# circuit.net
KiCad netlist of a schematic drawn in EAGLE
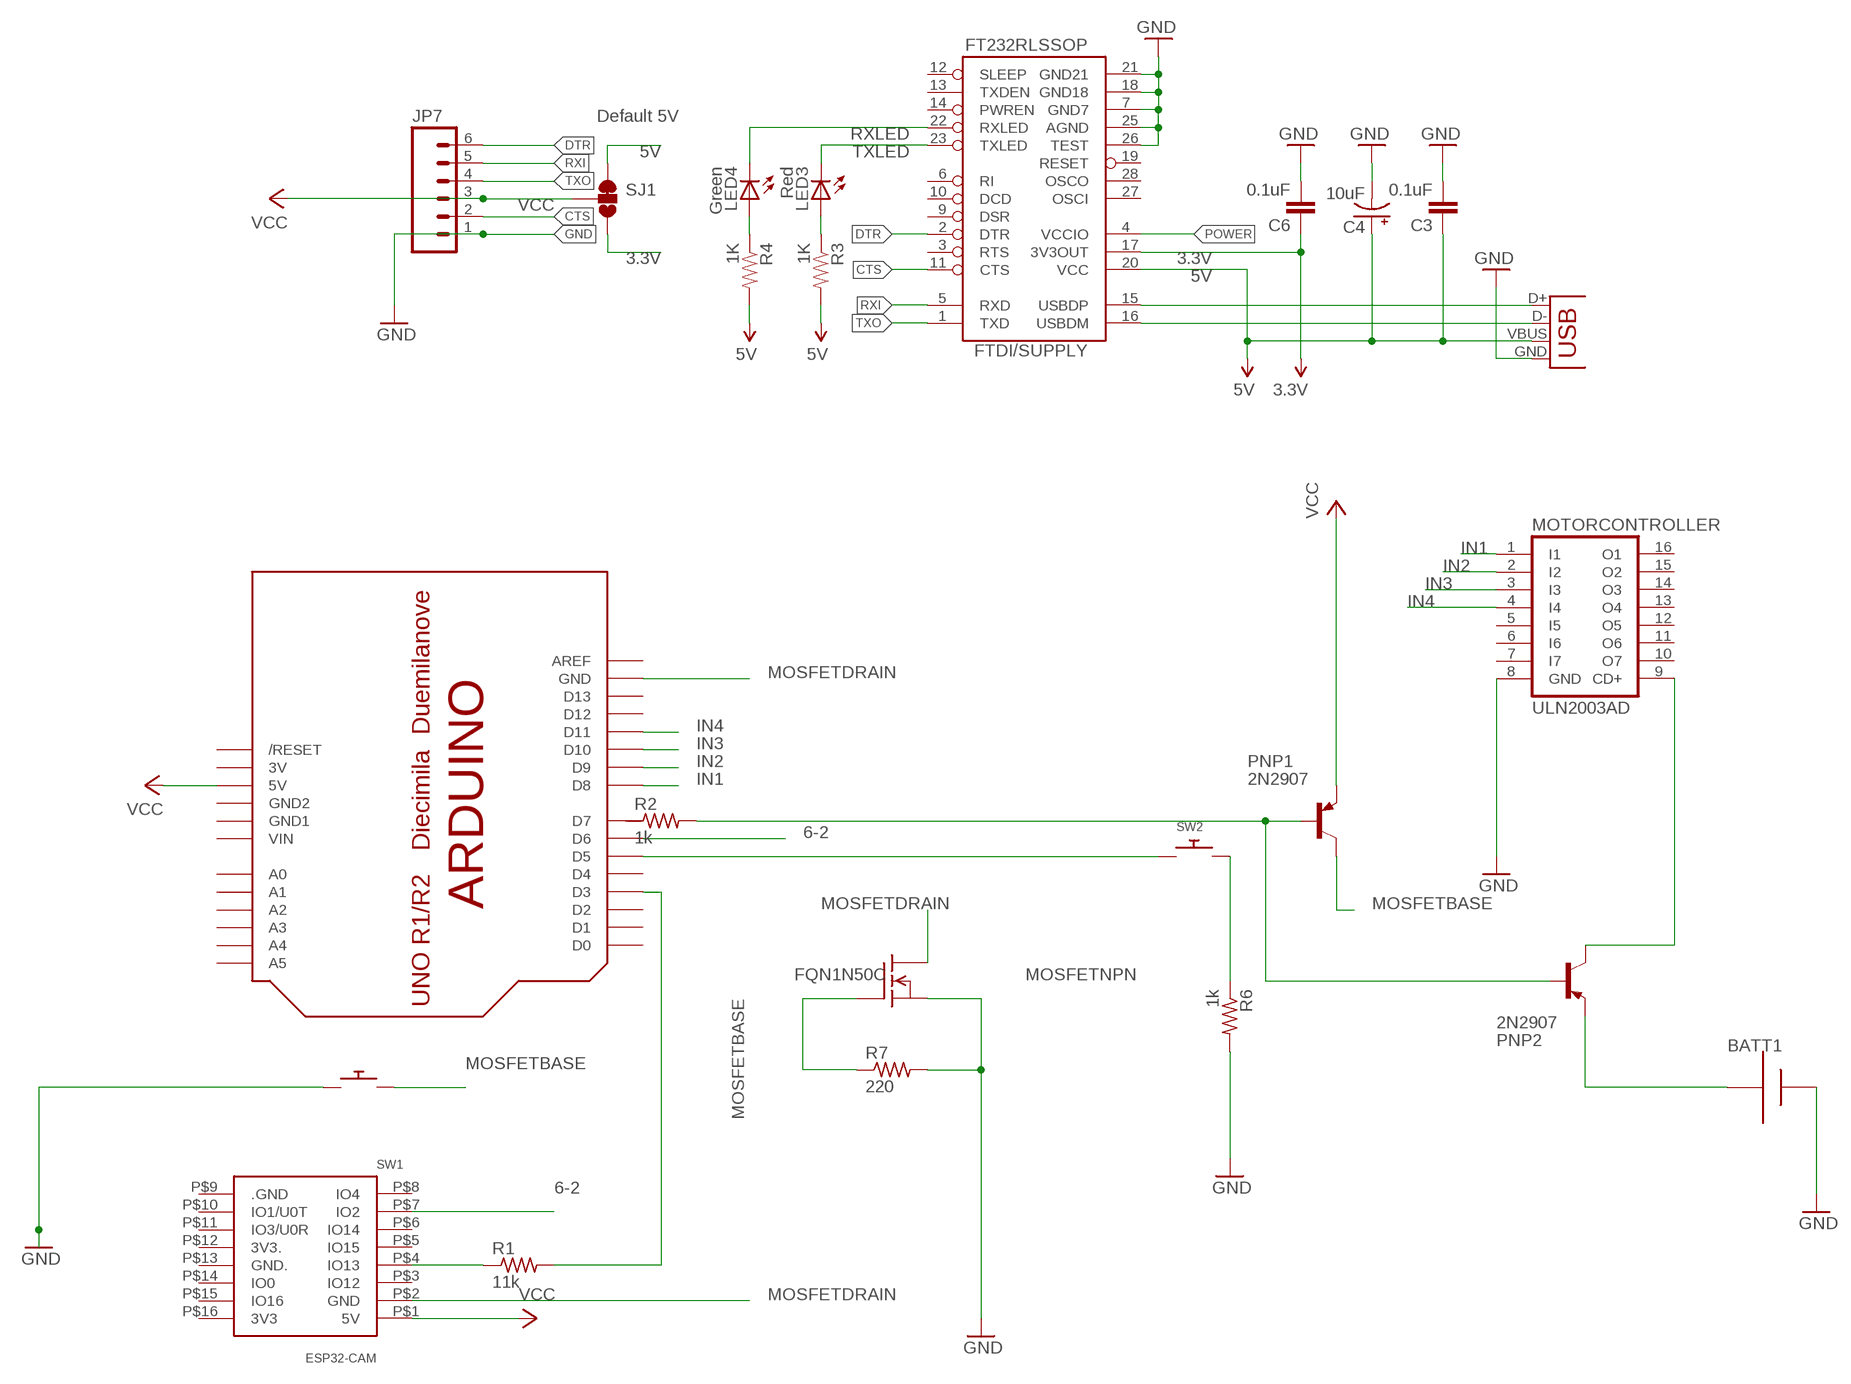
[diagram p0: schematic, sheet 1]

(export (version "E")
  (design (tool "Eeschema 10.0.6"))
  (components
    (comp (ref "BATT1")
      (value "AAA")
      (footprint "eagle-import:12BH412")
      (libsource (lib "eagle-import") (part "AAA"))
    )
    (comp (ref "C3")
      (value "0.1uF")
      (footprint "eagle-import:0603-CAP")
      (libsource (lib "eagle-import") (part "CAP0603-CAP"))
    )
    (comp (ref "C4")
      (value "10uF")
      (footprint "eagle-import:EIA3216")
      (libsource (lib "eagle-import") (part "CAP_POL1206"))
    )
    (comp (ref "C6")
      (value "0.1uF")
      (footprint "eagle-import:0603-CAP")
      (libsource (lib "eagle-import") (part "CAP0603-CAP"))
    )
    (comp (ref "ESP32-CAM")
      (value "ESP32-CAM")
      (footprint "eagle-import:ESP32-CAM")
      (fields (field (name "MF") "AI-Thinker"))
      (libsource (lib "eagle-import") (part "ESP32-CAM"))
    )
    (comp (ref "FTDI/SUPPLY")
      (value "FT232RLSSOP")
      (footprint "eagle-import:SSOP28DB")
      (libsource (lib "eagle-import") (part "FT232RLSSOP"))
    )
    (comp (ref "JP7")
      (value "M06SMD-FEMALE-V2")
      (footprint "eagle-import:1X06-SMD-FEMALE-V2")
      (libsource (lib "eagle-import") (part "M06SMD-FEMALE-V2"))
    )
    (comp (ref "LED3")
      (value "Red")
      (footprint "eagle-import:LED-0603")
      (libsource (lib "eagle-import") (part "LED0603"))
    )
    (comp (ref "LED4")
      (value "Green")
      (footprint "eagle-import:LED-0603")
      (libsource (lib "eagle-import") (part "LED0603"))
    )
    (comp (ref "MOSFETNPN")
      (value "FQN1N50C")
      (footprint "eagle-import:TO92")
      (libsource (lib "eagle-import") (part "FQN1N50C"))
    )
    (comp (ref "MOTORCONTROLLER")
      (value "ULN2003AD")
      (footprint "eagle-import:SO16")
      (libsource (lib "eagle-import") (part "ULN2003AD"))
    )
    (comp (ref "PNP1")
      (value "2N2907")
      (footprint "eagle-import:TO92-EBC-OVAL")
      (libsource (lib "eagle-import") (part "2N2907"))
    )
    (comp (ref "PNP2")
      (value "2N2907")
      (footprint "eagle-import:TO92-EBC-OVAL")
      (libsource (lib "eagle-import") (part "2N2907"))
    )
    (comp (ref "R1")
      (value "11k")
      (footprint "eagle-import:0204V")
      (libsource (lib "eagle-import") (part "R-US_0204/2V"))
    )
    (comp (ref "R2")
      (value "1k")
      (footprint "eagle-import:0805-THM")
      (libsource (lib "eagle-import") (part "FLIPFLOP-RES"))
    )
    (comp (ref "R3")
      (value "1K")
      (footprint "eagle-import:0603-RES")
      (libsource (lib "eagle-import") (part "RESISTOR0603-RES"))
    )
    (comp (ref "R4")
      (value "1K")
      (footprint "eagle-import:0603-RES")
      (libsource (lib "eagle-import") (part "RESISTOR0603-RES"))
    )
    (comp (ref "R6")
      (value "1k")
      (footprint "eagle-import:0805-THM")
      (libsource (lib "eagle-import") (part "FLIPFLOP-RES"))
    )
    (comp (ref "R7")
      (value "220")
      (footprint "eagle-import:0805-THM")
      (libsource (lib "eagle-import") (part "FLIPFLOP-RES"))
    )
    (comp (ref "SJ1")
      (value "SOLDERJUMPER_2WAYS")
      (footprint "eagle-import:SJ_3")
      (libsource (lib "eagle-import") (part "SOLDERJUMPER_2WAYS"))
    )
    (comp (ref "SW1")
      (value "SWITCH_PUSHBUTTONSOFTTOUCHSMD_SJ")
      (footprint "eagle-import:PUSHBUTTON_SMD_SJ")
      (libsource (lib "eagle-import") (part "SWITCH_PUSHBUTTONSOFTTOUCHSMD_SJ"))
    )
    (comp (ref "SW2")
      (value "SWITCH_PUSHBUTTONSOFTTOUCHSMD_SJ")
      (footprint "eagle-import:PUSHBUTTON_SMD_SJ")
      (libsource (lib "eagle-import") (part "SWITCH_PUSHBUTTONSOFTTOUCHSMD_SJ"))
    )
    (comp (ref "U$2")
      (value "ARDUINOUNO")
      (footprint "eagle-import:ARDUINO")
      (libsource (lib "eagle-import") (part "ARDUINOUNO"))
    )
    (comp (ref "X1")
      (value "USB-SMD-NS")
      (footprint "eagle-import:USB-MINIB-NOSTOP")
      (libsource (lib "eagle-import") (part "USB-SMD-NS"))
    )
  )
  (nets
    (net (code "1") (name "/3V") (class "Default")
      (node (ref "U$2") (pin "3V") (pinfunction "3V_3V") (pintype "power_in"))
    )
    (net (code "2") (name "/6-2") (class "Default")
      (node (ref "ESP32-CAM") (pin "P$7") (pinfunction "IO2_P$7") (pintype "bidirectional"))
      (node (ref "U$2") (pin "D6") (pinfunction "D6_D6") (pintype "bidirectional"))
    )
    (net (code "3") (name "/GND1") (class "Default")
      (node (ref "U$2") (pin "GND1") (pinfunction "GND1_GND1") (pintype "power_in"))
    )
    (net (code "4") (name "/GND2") (class "Default")
      (node (ref "U$2") (pin "GND2") (pinfunction "GND2_GND2") (pintype "power_in"))
    )
    (net (code "5") (name "/IN1") (class "Default")
      (node (ref "MOTORCONTROLLER") (pin "1") (pinfunction "I1_1") (pintype "input"))
      (node (ref "U$2") (pin "D8") (pinfunction "D8_D8") (pintype "bidirectional"))
    )
    (net (code "6") (name "/IN2") (class "Default")
      (node (ref "MOTORCONTROLLER") (pin "2") (pinfunction "I2_2") (pintype "input"))
      (node (ref "U$2") (pin "D9") (pinfunction "D9_D9") (pintype "bidirectional"))
    )
    (net (code "7") (name "/IN3") (class "Default")
      (node (ref "MOTORCONTROLLER") (pin "3") (pinfunction "I3_3") (pintype "input"))
      (node (ref "U$2") (pin "D10") (pinfunction "D10_D10") (pintype "bidirectional"))
    )
    (net (code "8") (name "/IN4") (class "Default")
      (node (ref "MOTORCONTROLLER") (pin "4") (pinfunction "I4_4") (pintype "input"))
      (node (ref "U$2") (pin "D11") (pinfunction "D11_D11") (pintype "bidirectional"))
    )
    (net (code "9") (name "/MOSFETBASE") (class "Default")
      (node (ref "MOSFETNPN") (pin "1") (pinfunction "G_1") (pintype "passive"))
      (node (ref "PNP1") (pin "C") (pinfunction "C_C") (pintype "passive"))
      (node (ref "R7") (pin "1") (pinfunction "1_1") (pintype "passive"))
      (node (ref "SW1") (pin "P$2") (pinfunction "P$2_P$2") (pintype "passive"))
    )
    (net (code "10") (name "/MOSFETDRAIN") (class "Default")
      (node (ref "ESP32-CAM") (pin "P$2") (pinfunction "GND_P$2") (pintype "bidirectional"))
      (node (ref "MOSFETNPN") (pin "2") (pinfunction "D_2") (pintype "passive"))
      (node (ref "U$2") (pin "GND") (pinfunction "GND_GND") (pintype "power_in"))
    )
    (net (code "11") (name "/RXLED") (class "Default")
      (node (ref "FTDI/SUPPLY") (pin "22") (pinfunction "RXLED_22") (pintype "input"))
      (node (ref "LED4") (pin "C") (pinfunction "C_C") (pintype "passive"))
    )
    (net (code "12") (name "/TXLED") (class "Default")
      (node (ref "FTDI/SUPPLY") (pin "23") (pinfunction "TXLED_23") (pintype "input"))
      (node (ref "LED3") (pin "C") (pinfunction "C_C") (pintype "passive"))
    )
    (net (code "13") (name "/VIN") (class "Default")
      (node (ref "U$2") (pin "VIN") (pinfunction "VIN_VIN") (pintype "power_in"))
    )
    (net (code "14") (name "3.3V") (class "Default")
      (node (ref "C6") (pin "1") (pinfunction "1_1") (pintype "passive"))
      (node (ref "FTDI/SUPPLY") (pin "17") (pinfunction "3V3OUT_17") (pintype "output"))
      (node (ref "SJ1") (pin "3") (pinfunction "3_3") (pintype "passive"))
    )
    (net (code "15") (name "5V") (class "Default")
      (node (ref "C3") (pin "1") (pinfunction "1_1") (pintype "passive"))
      (node (ref "C4") (pin "A") (pinfunction "+_A") (pintype "passive"))
      (node (ref "FTDI/SUPPLY") (pin "20") (pinfunction "VCC_20") (pintype "power_in"))
      (node (ref "R3") (pin "2") (pinfunction "2_2") (pintype "passive"))
      (node (ref "R4") (pin "2") (pinfunction "2_2") (pintype "passive"))
      (node (ref "SJ1") (pin "1") (pinfunction "1_1") (pintype "passive"))
      (node (ref "X1") (pin "VBUS") (pinfunction "VBUS_VBUS") (pintype "bidirectional"))
    )
    (net (code "16") (name "CTS") (class "Default")
      (node (ref "FTDI/SUPPLY") (pin "11") (pinfunction "CTS_11") (pintype "input"))
      (node (ref "JP7") (pin "2") (pinfunction "2_2") (pintype "passive"))
    )
    (net (code "17") (name "DTR") (class "Default")
      (node (ref "FTDI/SUPPLY") (pin "2") (pinfunction "DTR_2") (pintype "output"))
      (node (ref "JP7") (pin "6") (pinfunction "6_6") (pintype "passive"))
    )
    (net (code "18") (name "GND") (class "Default")
      (node (ref "BATT1") (pin "+") (pinfunction "+_+") (pintype "bidirectional"))
      (node (ref "C3") (pin "2") (pinfunction "2_2") (pintype "passive"))
      (node (ref "C4") (pin "C") (pinfunction "-_C") (pintype "passive"))
      (node (ref "C6") (pin "2") (pinfunction "2_2") (pintype "passive"))
      (node (ref "FTDI/SUPPLY") (pin "18") (pinfunction "GND18_18") (pintype "power_in"))
      (node (ref "FTDI/SUPPLY") (pin "21") (pinfunction "GND21_21") (pintype "power_in"))
      (node (ref "FTDI/SUPPLY") (pin "25") (pinfunction "AGND_25") (pintype "power_in"))
      (node (ref "FTDI/SUPPLY") (pin "26") (pinfunction "TEST_26") (pintype "input"))
      (node (ref "FTDI/SUPPLY") (pin "7") (pinfunction "GND7_7") (pintype "power_in"))
      (node (ref "JP7") (pin "1") (pinfunction "1_1") (pintype "passive"))
      (node (ref "MOSFETNPN") (pin "3") (pinfunction "S_3") (pintype "passive"))
      (node (ref "MOTORCONTROLLER") (pin "8") (pinfunction "GND_8") (pintype "power_in"))
      (node (ref "R6") (pin "2") (pinfunction "2_2") (pintype "passive"))
      (node (ref "R7") (pin "2") (pinfunction "2_2") (pintype "passive"))
      (node (ref "SW1") (pin "P$1") (pinfunction "P$1_P$1") (pintype "passive"))
      (node (ref "X1") (pin "GND") (pinfunction "GND_GND") (pintype "bidirectional"))
    )
    (net (code "19") (name "Net-(BATT1-Pad-)") (class "Default")
      (node (ref "BATT1") (pin "-") (pinfunction "-_-") (pintype "bidirectional"))
      (node (ref "PNP2") (pin "E") (pinfunction "E_E") (pintype "passive"))
    )
    (net (code "20") (name "Net-(ESP32-CAM-IO13)") (class "Default")
      (node (ref "ESP32-CAM") (pin "P$4") (pinfunction "IO13_P$4") (pintype "bidirectional"))
      (node (ref "R1") (pin "1") (pinfunction "1_1") (pintype "passive"))
    )
    (net (code "21") (name "Net-(FTDI/SUPPLY-USBDM)") (class "Default")
      (node (ref "FTDI/SUPPLY") (pin "16") (pinfunction "USBDM_16") (pintype "bidirectional"))
      (node (ref "X1") (pin "D-") (pinfunction "D-_D-") (pintype "bidirectional"))
    )
    (net (code "22") (name "Net-(FTDI/SUPPLY-USBDP)") (class "Default")
      (node (ref "FTDI/SUPPLY") (pin "15") (pinfunction "USBDP_15") (pintype "bidirectional"))
      (node (ref "X1") (pin "D+") (pinfunction "D+_D+") (pintype "bidirectional"))
    )
    (net (code "23") (name "Net-(LED3-PadA)") (class "Default")
      (node (ref "LED3") (pin "A") (pinfunction "A_A") (pintype "passive"))
      (node (ref "R3") (pin "1") (pinfunction "1_1") (pintype "passive"))
    )
    (net (code "24") (name "Net-(LED4-PadA)") (class "Default")
      (node (ref "LED4") (pin "A") (pinfunction "A_A") (pintype "passive"))
      (node (ref "R4") (pin "1") (pinfunction "1_1") (pintype "passive"))
    )
    (net (code "25") (name "Net-(MOTORCONTROLLER-CD+)") (class "Default")
      (node (ref "MOTORCONTROLLER") (pin "9") (pinfunction "CD+_9") (pintype "passive"))
      (node (ref "PNP2") (pin "C") (pinfunction "C_C") (pintype "passive"))
    )
    (net (code "26") (name "Net-(PNP1-PadB)") (class "Default")
      (node (ref "PNP1") (pin "B") (pinfunction "B_B") (pintype "passive"))
      (node (ref "PNP2") (pin "B") (pinfunction "B_B") (pintype "passive"))
      (node (ref "R2") (pin "2") (pinfunction "2_2") (pintype "passive"))
    )
    (net (code "27") (name "Net-(R1-Pad2)") (class "Default")
      (node (ref "R1") (pin "2") (pinfunction "2_2") (pintype "passive"))
      (node (ref "U$2") (pin "D3") (pinfunction "D3_D3") (pintype "bidirectional"))
    )
    (net (code "28") (name "Net-(R6-Pad1)") (class "Default")
      (node (ref "R6") (pin "1") (pinfunction "1_1") (pintype "passive"))
      (node (ref "SW2") (pin "P$2") (pinfunction "P$2_P$2") (pintype "passive"))
    )
    (net (code "29") (name "Net-(SW2-PadP$1)") (class "Default")
      (node (ref "SW2") (pin "P$1") (pinfunction "P$1_P$1") (pintype "passive"))
      (node (ref "U$2") (pin "D5") (pinfunction "D5_D5") (pintype "bidirectional"))
    )
    (net (code "30") (name "POWER") (class "Default")
      (node (ref "FTDI/SUPPLY") (pin "4") (pinfunction "VCCIO_4") (pintype "power_in"))
    )
    (net (code "31") (name "RXI") (class "Default")
      (node (ref "FTDI/SUPPLY") (pin "5") (pinfunction "RXD_5") (pintype "input"))
      (node (ref "JP7") (pin "5") (pinfunction "5_5") (pintype "passive"))
    )
    (net (code "32") (name "TXO") (class "Default")
      (node (ref "FTDI/SUPPLY") (pin "1") (pinfunction "TXD_1") (pintype "output"))
      (node (ref "JP7") (pin "4") (pinfunction "4_4") (pintype "passive"))
    )
    (net (code "33") (name "VCC") (class "Default")
      (node (ref "ESP32-CAM") (pin "P$1") (pinfunction "5V_P$1") (pintype "bidirectional"))
      (node (ref "JP7") (pin "3") (pinfunction "3_3") (pintype "passive"))
      (node (ref "PNP1") (pin "E") (pinfunction "E_E") (pintype "passive"))
      (node (ref "SJ1") (pin "2") (pinfunction "2_2") (pintype "passive"))
      (node (ref "U$2") (pin "5V") (pinfunction "5V_5V") (pintype "power_in"))
    )
    (net (code "34") (name "unconnected-(ESP32-CAM-.GND-PadP$9)") (class "Default")
      (node (ref "ESP32-CAM") (pin "P$9") (pinfunction ".GND_P$9") (pintype "bidirectional"))
    )
    (net (code "35") (name "unconnected-(ESP32-CAM-3V3-PadP$16)") (class "Default")
      (node (ref "ESP32-CAM") (pin "P$16") (pinfunction "3V3_P$16") (pintype "bidirectional"))
    )
    (net (code "36") (name "unconnected-(ESP32-CAM-3V3.-PadP$12)") (class "Default")
      (node (ref "ESP32-CAM") (pin "P$12") (pinfunction "3V3._P$12") (pintype "bidirectional"))
    )
    (net (code "37") (name "unconnected-(ESP32-CAM-GND.-PadP$13)") (class "Default")
      (node (ref "ESP32-CAM") (pin "P$13") (pinfunction "GND._P$13") (pintype "bidirectional"))
    )
    (net (code "38") (name "unconnected-(ESP32-CAM-IO0-PadP$14)") (class "Default")
      (node (ref "ESP32-CAM") (pin "P$14") (pinfunction "IO0_P$14") (pintype "bidirectional"))
    )
    (net (code "39") (name "unconnected-(ESP32-CAM-IO1{slash}U0T-PadP$10)") (class "Default")
      (node (ref "ESP32-CAM") (pin "P$10") (pinfunction "IO1/U0T_P$10") (pintype "bidirectional"))
    )
    (net (code "40") (name "unconnected-(ESP32-CAM-IO3{slash}U0R-PadP$11)") (class "Default")
      (node (ref "ESP32-CAM") (pin "P$11") (pinfunction "IO3/U0R_P$11") (pintype "bidirectional"))
    )
    (net (code "41") (name "unconnected-(ESP32-CAM-IO4-PadP$8)") (class "Default")
      (node (ref "ESP32-CAM") (pin "P$8") (pinfunction "IO4_P$8") (pintype "bidirectional"))
    )
    (net (code "42") (name "unconnected-(ESP32-CAM-IO12-PadP$3)") (class "Default")
      (node (ref "ESP32-CAM") (pin "P$3") (pinfunction "IO12_P$3") (pintype "bidirectional"))
    )
    (net (code "43") (name "unconnected-(ESP32-CAM-IO14-PadP$6)") (class "Default")
      (node (ref "ESP32-CAM") (pin "P$6") (pinfunction "IO14_P$6") (pintype "bidirectional"))
    )
    (net (code "44") (name "unconnected-(ESP32-CAM-IO15-PadP$5)") (class "Default")
      (node (ref "ESP32-CAM") (pin "P$5") (pinfunction "IO15_P$5") (pintype "bidirectional"))
    )
    (net (code "45") (name "unconnected-(ESP32-CAM-IO16-PadP$15)") (class "Default")
      (node (ref "ESP32-CAM") (pin "P$15") (pinfunction "IO16_P$15") (pintype "bidirectional"))
    )
    (net (code "46") (name "unconnected-(FTDI/SUPPLY-DCD-Pad10)") (class "Default")
      (node (ref "FTDI/SUPPLY") (pin "10") (pinfunction "DCD_10") (pintype "input"))
    )
    (net (code "47") (name "unconnected-(FTDI/SUPPLY-DSR-Pad9)") (class "Default")
      (node (ref "FTDI/SUPPLY") (pin "9") (pinfunction "DSR_9") (pintype "input"))
    )
    (net (code "48") (name "unconnected-(FTDI/SUPPLY-OSCI-Pad27)") (class "Default")
      (node (ref "FTDI/SUPPLY") (pin "27") (pinfunction "OSCI_27") (pintype "input"))
    )
    (net (code "49") (name "unconnected-(FTDI/SUPPLY-OSCO-Pad28)") (class "Default")
      (node (ref "FTDI/SUPPLY") (pin "28") (pinfunction "OSCO_28") (pintype "output"))
    )
    (net (code "50") (name "unconnected-(FTDI/SUPPLY-PWREN-Pad14)") (class "Default")
      (node (ref "FTDI/SUPPLY") (pin "14") (pinfunction "PWREN_14") (pintype "input"))
    )
    (net (code "51") (name "unconnected-(FTDI/SUPPLY-RESET-Pad19)") (class "Default")
      (node (ref "FTDI/SUPPLY") (pin "19") (pinfunction "RESET_19") (pintype "input"))
    )
    (net (code "52") (name "unconnected-(FTDI/SUPPLY-RI-Pad6)") (class "Default")
      (node (ref "FTDI/SUPPLY") (pin "6") (pinfunction "RI_6") (pintype "input"))
    )
    (net (code "53") (name "unconnected-(FTDI/SUPPLY-RTS-Pad3)") (class "Default")
      (node (ref "FTDI/SUPPLY") (pin "3") (pinfunction "RTS_3") (pintype "output"))
    )
    (net (code "54") (name "unconnected-(FTDI/SUPPLY-SLEEP-Pad12)") (class "Default")
      (node (ref "FTDI/SUPPLY") (pin "12") (pinfunction "SLEEP_12") (pintype "input"))
    )
    (net (code "55") (name "unconnected-(FTDI/SUPPLY-TXDEN-Pad13)") (class "Default")
      (node (ref "FTDI/SUPPLY") (pin "13") (pinfunction "TXDEN_13") (pintype "input"))
    )
    (net (code "56") (name "unconnected-(MOTORCONTROLLER-I5-Pad5)") (class "Default")
      (node (ref "MOTORCONTROLLER") (pin "5") (pinfunction "I5_5") (pintype "input"))
    )
    (net (code "57") (name "unconnected-(MOTORCONTROLLER-I6-Pad6)") (class "Default")
      (node (ref "MOTORCONTROLLER") (pin "6") (pinfunction "I6_6") (pintype "input"))
    )
    (net (code "58") (name "unconnected-(MOTORCONTROLLER-I7-Pad7)") (class "Default")
      (node (ref "MOTORCONTROLLER") (pin "7") (pinfunction "I7_7") (pintype "input"))
    )
    (net (code "59") (name "unconnected-(MOTORCONTROLLER-O1-Pad16)") (class "Default")
      (node (ref "MOTORCONTROLLER") (pin "16") (pinfunction "O1_16") (pintype "open_collector"))
    )
    (net (code "60") (name "unconnected-(MOTORCONTROLLER-O2-Pad15)") (class "Default")
      (node (ref "MOTORCONTROLLER") (pin "15") (pinfunction "O2_15") (pintype "open_collector"))
    )
    (net (code "61") (name "unconnected-(MOTORCONTROLLER-O3-Pad14)") (class "Default")
      (node (ref "MOTORCONTROLLER") (pin "14") (pinfunction "O3_14") (pintype "open_collector"))
    )
    (net (code "62") (name "unconnected-(MOTORCONTROLLER-O4-Pad13)") (class "Default")
      (node (ref "MOTORCONTROLLER") (pin "13") (pinfunction "O4_13") (pintype "open_collector"))
    )
    (net (code "63") (name "unconnected-(MOTORCONTROLLER-O5-Pad12)") (class "Default")
      (node (ref "MOTORCONTROLLER") (pin "12") (pinfunction "O5_12") (pintype "open_collector"))
    )
    (net (code "64") (name "unconnected-(MOTORCONTROLLER-O6-Pad11)") (class "Default")
      (node (ref "MOTORCONTROLLER") (pin "11") (pinfunction "O6_11") (pintype "open_collector"))
    )
    (net (code "65") (name "unconnected-(MOTORCONTROLLER-O7-Pad10)") (class "Default")
      (node (ref "MOTORCONTROLLER") (pin "10") (pinfunction "O7_10") (pintype "open_collector"))
    )
    (net (code "66") (name "unconnected-(R2-Pad1)") (class "Default")
      (node (ref "R2") (pin "1") (pinfunction "1_1") (pintype "passive"))
    )
    (net (code "67") (name "unconnected-(U$2-PadA0)") (class "Default")
      (node (ref "U$2") (pin "A0") (pinfunction "A0_A0") (pintype "bidirectional"))
    )
    (net (code "68") (name "unconnected-(U$2-PadA1)") (class "Default")
      (node (ref "U$2") (pin "A1") (pinfunction "A1_A1") (pintype "bidirectional"))
    )
    (net (code "69") (name "unconnected-(U$2-PadA2)") (class "Default")
      (node (ref "U$2") (pin "A2") (pinfunction "A2_A2") (pintype "bidirectional"))
    )
    (net (code "70") (name "unconnected-(U$2-PadA3)") (class "Default")
      (node (ref "U$2") (pin "A3") (pinfunction "A3_A3") (pintype "bidirectional"))
    )
    (net (code "71") (name "unconnected-(U$2-PadA4)") (class "Default")
      (node (ref "U$2") (pin "A4") (pinfunction "A4_A4") (pintype "bidirectional"))
    )
    (net (code "72") (name "unconnected-(U$2-PadA5)") (class "Default")
      (node (ref "U$2") (pin "A5") (pinfunction "A5_A5") (pintype "bidirectional"))
    )
    (net (code "73") (name "unconnected-(U$2-PadAREF)") (class "Default")
      (node (ref "U$2") (pin "AREF") (pinfunction "AREF_AREF") (pintype "bidirectional"))
    )
    (net (code "74") (name "unconnected-(U$2-PadD0)") (class "Default")
      (node (ref "U$2") (pin "D0") (pinfunction "D0_D0") (pintype "bidirectional"))
    )
    (net (code "75") (name "unconnected-(U$2-PadD1)") (class "Default")
      (node (ref "U$2") (pin "D1") (pinfunction "D1_D1") (pintype "bidirectional"))
    )
    (net (code "76") (name "unconnected-(U$2-PadD2)") (class "Default")
      (node (ref "U$2") (pin "D2") (pinfunction "D2_D2") (pintype "bidirectional"))
    )
    (net (code "77") (name "unconnected-(U$2-PadD4)") (class "Default")
      (node (ref "U$2") (pin "D4") (pinfunction "D4_D4") (pintype "bidirectional"))
    )
    (net (code "78") (name "unconnected-(U$2-PadD7)") (class "Default")
      (node (ref "U$2") (pin "D7") (pinfunction "D7_D7") (pintype "bidirectional"))
    )
    (net (code "79") (name "unconnected-(U$2-PadD12)") (class "Default")
      (node (ref "U$2") (pin "D12") (pinfunction "D12_D12") (pintype "bidirectional"))
    )
    (net (code "80") (name "unconnected-(U$2-PadD13)") (class "Default")
      (node (ref "U$2") (pin "D13") (pinfunction "D13_D13") (pintype "bidirectional"))
    )
    (net (code "81") (name "unconnected-(U$2-{slash}RESET-PadRESET)") (class "Default")
      (node (ref "U$2") (pin "RESET") (pinfunction "/RESET_RESET") (pintype "bidirectional"))
    )
  )
)
